# Tracker_V3.net
KiCad netlist of a schematic drawn in EAGLE
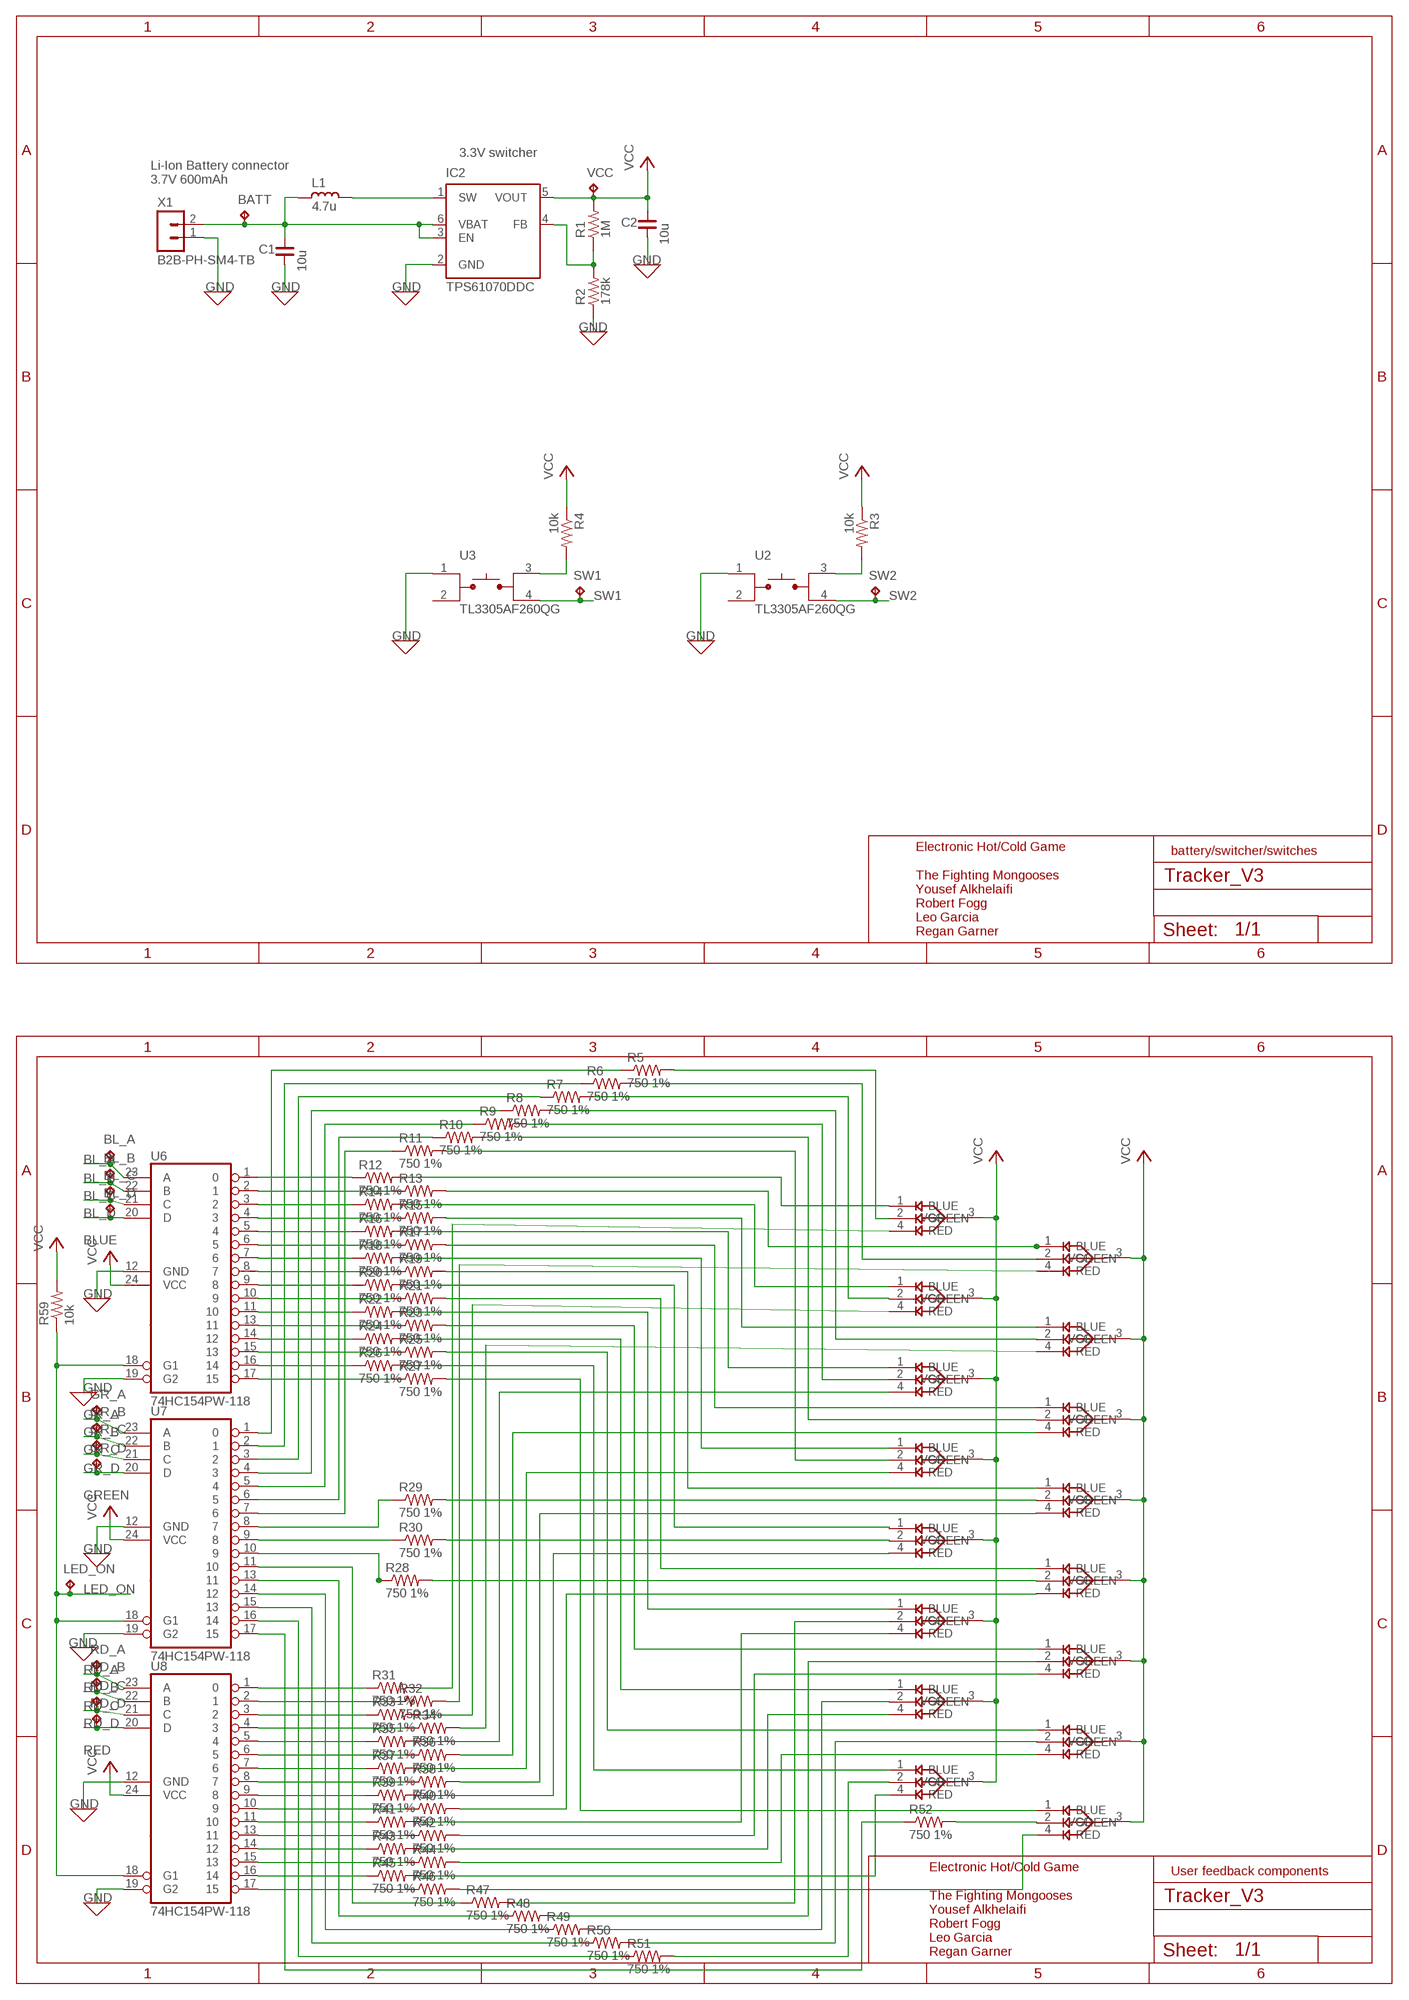
[diagram p0: schematic, sheet 1, part 1 of 2]
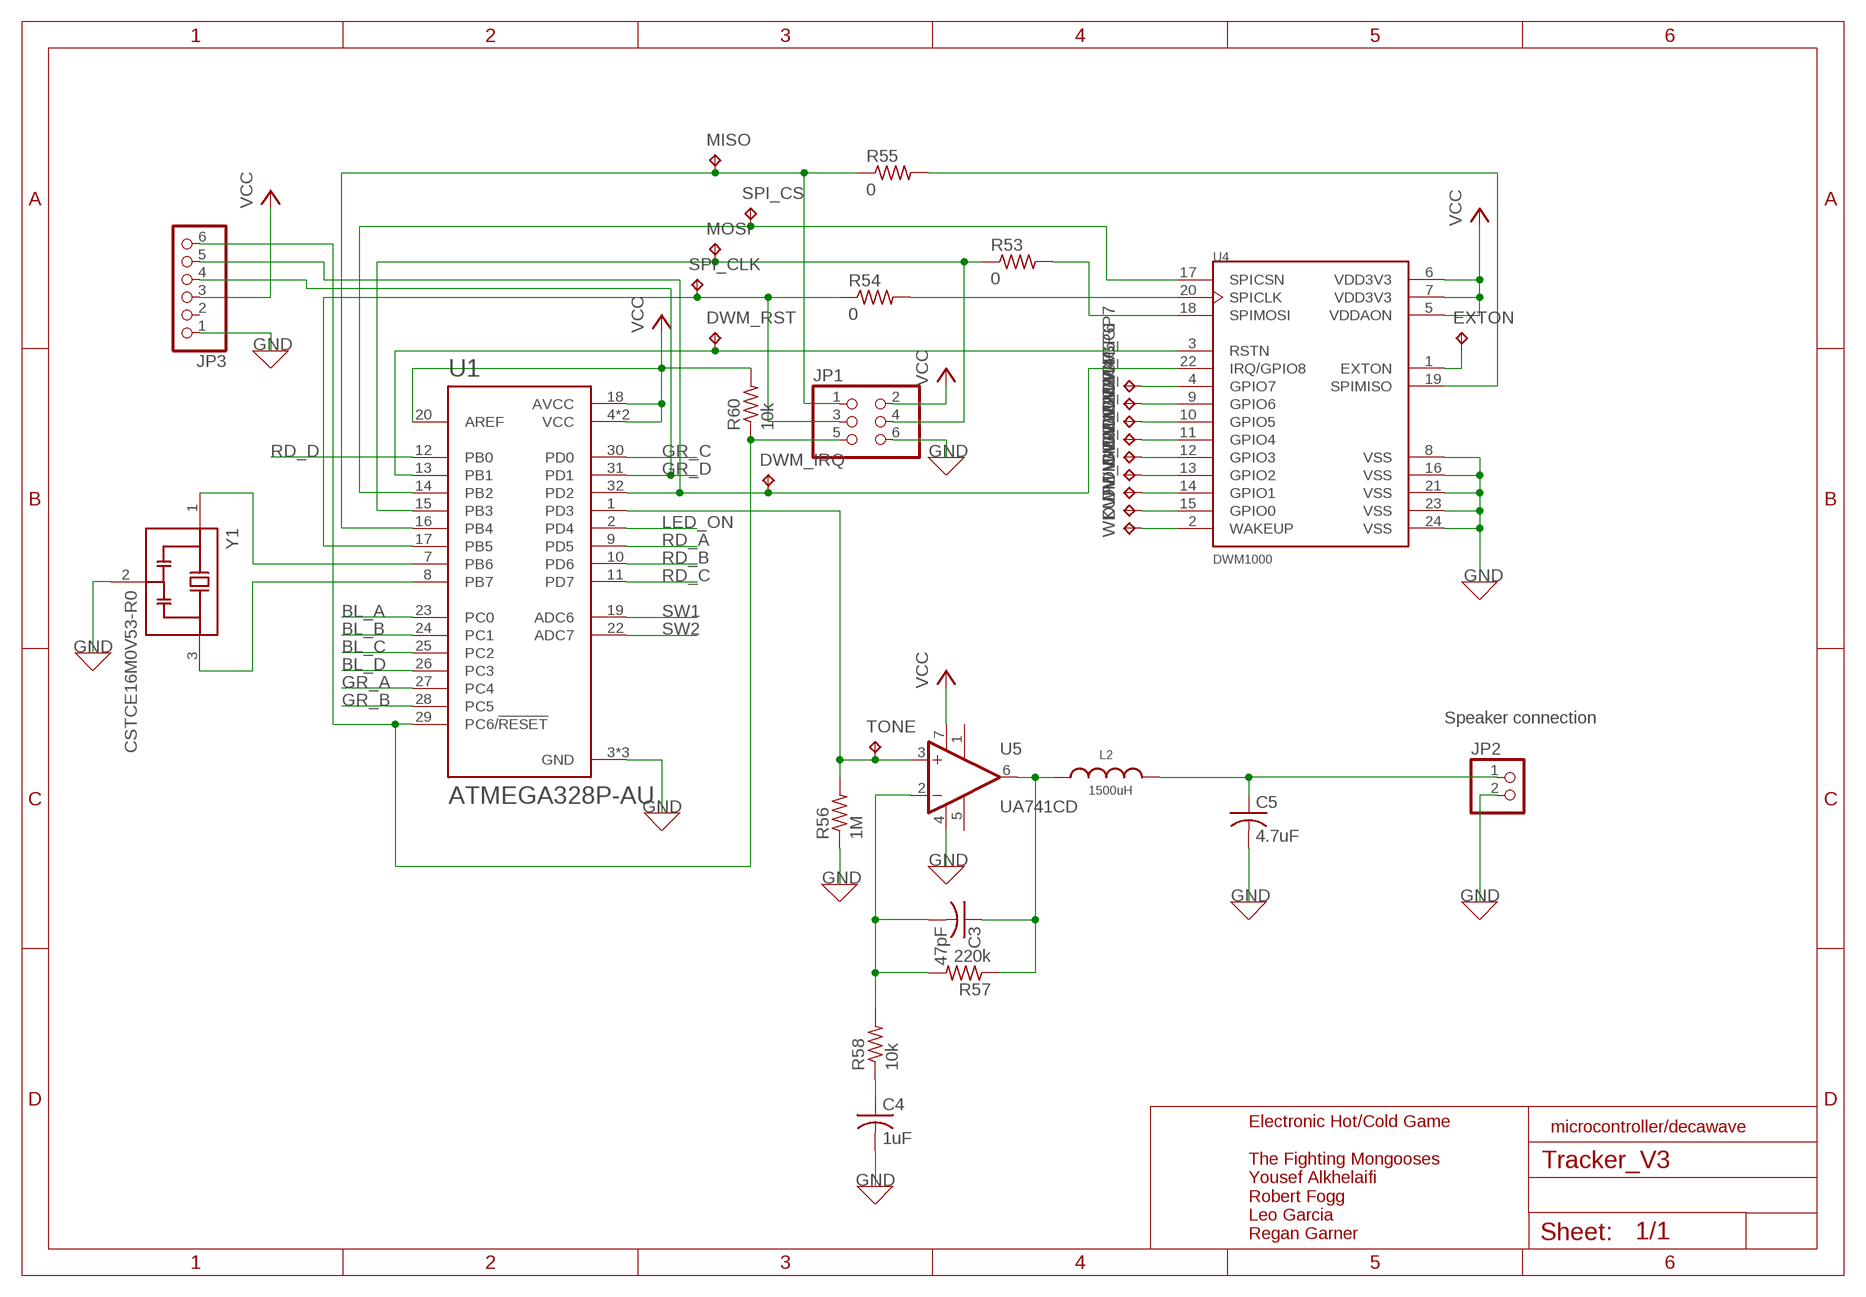
[diagram p1: schematic, sheet 1, part 2 of 2]

(export (version "E")
  (design (tool "Eeschema 10.0.6"))
  (components
    (comp (ref "BATT")
      (value "TPB2,54")
      (footprint "eagle-import:B2,54")
      (libsource (lib "eagle-import") (part "TPB2,54"))
    )
    (comp (ref "BL_A")
      (value "TPB2,54")
      (footprint "eagle-import:B2,54")
      (libsource (lib "eagle-import") (part "TPB2,54"))
    )
    (comp (ref "BL_B")
      (value "TPB2,54")
      (footprint "eagle-import:B2,54")
      (libsource (lib "eagle-import") (part "TPB2,54"))
    )
    (comp (ref "BL_C")
      (value "TPB2,54")
      (footprint "eagle-import:B2,54")
      (libsource (lib "eagle-import") (part "TPB2,54"))
    )
    (comp (ref "BL_D")
      (value "TPB2,54")
      (footprint "eagle-import:B2,54")
      (libsource (lib "eagle-import") (part "TPB2,54"))
    )
    (comp (ref "C1")
      (value "10u")
      (footprint "eagle-import:C0603")
      (fields (field (name "C1") "10uF"))
      (libsource (lib "eagle-import") (part "C_0603"))
    )
    (comp (ref "C2")
      (value "10u")
      (footprint "eagle-import:C0603")
      (fields (field (name "C1") "10uF"))
      (libsource (lib "eagle-import") (part "C_0603"))
    )
    (comp (ref "C3")
      (value "47pF")
      (footprint "eagle-import:C0402")
      (libsource (lib "eagle-import") (part "C-USC0402"))
    )
    (comp (ref "C4")
      (value "1uF")
      (footprint "eagle-import:C0402")
      (libsource (lib "eagle-import") (part "C-USC0402"))
    )
    (comp (ref "C5")
      (value "4.7uF")
      (footprint "eagle-import:C0402")
      (libsource (lib "eagle-import") (part "C-USC0402"))
    )
    (comp (ref "D1")
      (value "LED_EAST1616RGBA3")
      (footprint "eagle-import:LED_EAST1616RGBA3")
      (libsource (lib "eagle-import") (part "LED_EAST1616RGBA3"))
    )
    (comp (ref "D2")
      (value "LED_EAST1616RGBA3")
      (footprint "eagle-import:LED_EAST1616RGBA3")
      (libsource (lib "eagle-import") (part "LED_EAST1616RGBA3"))
    )
    (comp (ref "D3")
      (value "LED_EAST1616RGBA3")
      (footprint "eagle-import:LED_EAST1616RGBA3")
      (libsource (lib "eagle-import") (part "LED_EAST1616RGBA3"))
    )
    (comp (ref "D4")
      (value "LED_EAST1616RGBA3")
      (footprint "eagle-import:LED_EAST1616RGBA3")
      (libsource (lib "eagle-import") (part "LED_EAST1616RGBA3"))
    )
    (comp (ref "D5")
      (value "LED_EAST1616RGBA3")
      (footprint "eagle-import:LED_EAST1616RGBA3")
      (libsource (lib "eagle-import") (part "LED_EAST1616RGBA3"))
    )
    (comp (ref "D6")
      (value "LED_EAST1616RGBA3")
      (footprint "eagle-import:LED_EAST1616RGBA3")
      (libsource (lib "eagle-import") (part "LED_EAST1616RGBA3"))
    )
    (comp (ref "D7")
      (value "LED_EAST1616RGBA3")
      (footprint "eagle-import:LED_EAST1616RGBA3")
      (libsource (lib "eagle-import") (part "LED_EAST1616RGBA3"))
    )
    (comp (ref "D8")
      (value "LED_EAST1616RGBA3")
      (footprint "eagle-import:LED_EAST1616RGBA3")
      (libsource (lib "eagle-import") (part "LED_EAST1616RGBA3"))
    )
    (comp (ref "D9")
      (value "LED_EAST1616RGBA3")
      (footprint "eagle-import:LED_EAST1616RGBA3")
      (libsource (lib "eagle-import") (part "LED_EAST1616RGBA3"))
    )
    (comp (ref "D10")
      (value "LED_EAST1616RGBA3")
      (footprint "eagle-import:LED_EAST1616RGBA3")
      (libsource (lib "eagle-import") (part "LED_EAST1616RGBA3"))
    )
    (comp (ref "D11")
      (value "LED_EAST1616RGBA3")
      (footprint "eagle-import:LED_EAST1616RGBA3")
      (libsource (lib "eagle-import") (part "LED_EAST1616RGBA3"))
    )
    (comp (ref "D12")
      (value "LED_EAST1616RGBA3")
      (footprint "eagle-import:LED_EAST1616RGBA3")
      (libsource (lib "eagle-import") (part "LED_EAST1616RGBA3"))
    )
    (comp (ref "D13")
      (value "LED_EAST1616RGBA3")
      (footprint "eagle-import:LED_EAST1616RGBA3")
      (libsource (lib "eagle-import") (part "LED_EAST1616RGBA3"))
    )
    (comp (ref "D14")
      (value "LED_EAST1616RGBA3")
      (footprint "eagle-import:LED_EAST1616RGBA3")
      (libsource (lib "eagle-import") (part "LED_EAST1616RGBA3"))
    )
    (comp (ref "D15")
      (value "LED_EAST1616RGBA3")
      (footprint "eagle-import:LED_EAST1616RGBA3")
      (libsource (lib "eagle-import") (part "LED_EAST1616RGBA3"))
    )
    (comp (ref "D16")
      (value "LED_EAST1616RGBA3")
      (footprint "eagle-import:LED_EAST1616RGBA3")
      (libsource (lib "eagle-import") (part "LED_EAST1616RGBA3"))
    )
    (comp (ref "DWM_GP0")
      (value "TPB2,54")
      (footprint "eagle-import:B2,54")
      (libsource (lib "eagle-import") (part "TPB2,54"))
    )
    (comp (ref "DWM_GP1")
      (value "TPB2,54")
      (footprint "eagle-import:B2,54")
      (libsource (lib "eagle-import") (part "TPB2,54"))
    )
    (comp (ref "DWM_GP2")
      (value "TPB2,54")
      (footprint "eagle-import:B2,54")
      (libsource (lib "eagle-import") (part "TPB2,54"))
    )
    (comp (ref "DWM_GP3")
      (value "TPB2,54")
      (footprint "eagle-import:B2,54")
      (libsource (lib "eagle-import") (part "TPB2,54"))
    )
    (comp (ref "DWM_GP4")
      (value "TPB2,54")
      (footprint "eagle-import:B2,54")
      (libsource (lib "eagle-import") (part "TPB2,54"))
    )
    (comp (ref "DWM_GP5")
      (value "TPB2,54")
      (footprint "eagle-import:B2,54")
      (libsource (lib "eagle-import") (part "TPB2,54"))
    )
    (comp (ref "DWM_GP6")
      (value "TPB2,54")
      (footprint "eagle-import:B2,54")
      (libsource (lib "eagle-import") (part "TPB2,54"))
    )
    (comp (ref "DWM_GP7")
      (value "TPB2,54")
      (footprint "eagle-import:B2,54")
      (libsource (lib "eagle-import") (part "TPB2,54"))
    )
    (comp (ref "DWM_IRQ")
      (value "TPB2,54")
      (footprint "eagle-import:B2,54")
      (libsource (lib "eagle-import") (part "TPB2,54"))
    )
    (comp (ref "DWM_RST")
      (value "TPB2,54")
      (footprint "eagle-import:B2,54")
      (libsource (lib "eagle-import") (part "TPB2,54"))
    )
    (comp (ref "EXTON")
      (value "TPB2,54")
      (footprint "eagle-import:B2,54")
      (libsource (lib "eagle-import") (part "TPB2,54"))
    )
    (comp (ref "GR_A")
      (value "TPB2,54")
      (footprint "eagle-import:B2,54")
      (libsource (lib "eagle-import") (part "TPB2,54"))
    )
    (comp (ref "GR_B")
      (value "TPB2,54")
      (footprint "eagle-import:B2,54")
      (libsource (lib "eagle-import") (part "TPB2,54"))
    )
    (comp (ref "GR_C")
      (value "TPB2,54")
      (footprint "eagle-import:B2,54")
      (libsource (lib "eagle-import") (part "TPB2,54"))
    )
    (comp (ref "GR_D")
      (value "TPB2,54")
      (footprint "eagle-import:B2,54")
      (libsource (lib "eagle-import") (part "TPB2,54"))
    )
    (comp (ref "IC2")
      (value "TPS61070DDC")
      (footprint "eagle-import:TSOT23-6_DDC")
      (fields (field (name "MPN") "TPS61070DDCR"))
      (libsource (lib "eagle-import") (part "TPS6107DDC0"))
    )
    (comp (ref "JP1")
      (value "PINHD-2X3")
      (footprint "eagle-import:2X03")
      (libsource (lib "eagle-import") (part "PINHD-2X3"))
    )
    (comp (ref "JP2")
      (value "PINHD-1X2")
      (footprint "eagle-import:1X02")
      (libsource (lib "eagle-import") (part "PINHD-1X2"))
    )
    (comp (ref "JP3")
      (value "PINHD-1X6")
      (footprint "eagle-import:1X06")
      (libsource (lib "eagle-import") (part "PINHD-1X6"))
    )
    (comp (ref "L1")
      (value "4.7u")
      (footprint "eagle-import:L0603")
      (fields (field (name "L1") "4.7uH"))
      (libsource (lib "eagle-import") (part "L_0603"))
    )
    (comp (ref "L2")
      (value "1500uH")
      (footprint "eagle-import:WE-TPC_4828")
      (libsource (lib "eagle-import") (part "WE-TPC_4828_744043152"))
    )
    (comp (ref "LED_ON")
      (value "TPB2,54")
      (footprint "eagle-import:B2,54")
      (libsource (lib "eagle-import") (part "TPB2,54"))
    )
    (comp (ref "MISO")
      (value "TPB2,54")
      (footprint "eagle-import:B2,54")
      (libsource (lib "eagle-import") (part "TPB2,54"))
    )
    (comp (ref "MOSI")
      (value "TPB2,54")
      (footprint "eagle-import:B2,54")
      (libsource (lib "eagle-import") (part "TPB2,54"))
    )
    (comp (ref "R1")
      (value "1M")
      (footprint "eagle-import:R0603")
      (libsource (lib "eagle-import") (part "R_0603"))
    )
    (comp (ref "R2")
      (value "178k")
      (footprint "eagle-import:R0603")
      (libsource (lib "eagle-import") (part "R_0603"))
    )
    (comp (ref "R3")
      (value "10k")
      (footprint "eagle-import:R0603")
      (libsource (lib "eagle-import") (part "resistor_348_R-US_R0603"))
    )
    (comp (ref "R4")
      (value "10k")
      (footprint "eagle-import:R0603")
      (libsource (lib "eagle-import") (part "resistor_348_R-US_R0603"))
    )
    (comp (ref "R5")
      (value "750 1%")
      (footprint "eagle-import:R0402")
      (libsource (lib "eagle-import") (part "resistor_348_R-US_R0402"))
    )
    (comp (ref "R6")
      (value "750 1%")
      (footprint "eagle-import:R0402")
      (libsource (lib "eagle-import") (part "resistor_348_R-US_R0402"))
    )
    (comp (ref "R7")
      (value "750 1%")
      (footprint "eagle-import:R0402")
      (libsource (lib "eagle-import") (part "resistor_348_R-US_R0402"))
    )
    (comp (ref "R8")
      (value "750 1%")
      (footprint "eagle-import:R0402")
      (libsource (lib "eagle-import") (part "resistor_348_R-US_R0402"))
    )
    (comp (ref "R9")
      (value "750 1%")
      (footprint "eagle-import:R0402")
      (libsource (lib "eagle-import") (part "resistor_348_R-US_R0402"))
    )
    (comp (ref "R10")
      (value "750 1%")
      (footprint "eagle-import:R0402")
      (libsource (lib "eagle-import") (part "resistor_348_R-US_R0402"))
    )
    (comp (ref "R11")
      (value "750 1%")
      (footprint "eagle-import:R0402")
      (libsource (lib "eagle-import") (part "resistor_348_R-US_R0402"))
    )
    (comp (ref "R12")
      (value "750 1%")
      (footprint "eagle-import:R0402")
      (libsource (lib "eagle-import") (part "resistor_348_R-US_R0402"))
    )
    (comp (ref "R13")
      (value "750 1%")
      (footprint "eagle-import:R0402")
      (libsource (lib "eagle-import") (part "resistor_348_R-US_R0402"))
    )
    (comp (ref "R14")
      (value "750 1%")
      (footprint "eagle-import:R0402")
      (libsource (lib "eagle-import") (part "resistor_348_R-US_R0402"))
    )
    (comp (ref "R15")
      (value "750 1%")
      (footprint "eagle-import:R0402")
      (libsource (lib "eagle-import") (part "resistor_348_R-US_R0402"))
    )
    (comp (ref "R16")
      (value "750 1%")
      (footprint "eagle-import:R0402")
      (libsource (lib "eagle-import") (part "resistor_348_R-US_R0402"))
    )
    (comp (ref "R17")
      (value "750 1%")
      (footprint "eagle-import:R0402")
      (libsource (lib "eagle-import") (part "resistor_348_R-US_R0402"))
    )
    (comp (ref "R18")
      (value "750 1%")
      (footprint "eagle-import:R0402")
      (libsource (lib "eagle-import") (part "resistor_348_R-US_R0402"))
    )
    (comp (ref "R19")
      (value "750 1%")
      (footprint "eagle-import:R0402")
      (libsource (lib "eagle-import") (part "resistor_348_R-US_R0402"))
    )
    (comp (ref "R20")
      (value "750 1%")
      (footprint "eagle-import:R0402")
      (libsource (lib "eagle-import") (part "resistor_348_R-US_R0402"))
    )
    (comp (ref "R21")
      (value "750 1%")
      (footprint "eagle-import:R0402")
      (libsource (lib "eagle-import") (part "resistor_348_R-US_R0402"))
    )
    (comp (ref "R22")
      (value "750 1%")
      (footprint "eagle-import:R0402")
      (libsource (lib "eagle-import") (part "resistor_348_R-US_R0402"))
    )
    (comp (ref "R23")
      (value "750 1%")
      (footprint "eagle-import:R0402")
      (libsource (lib "eagle-import") (part "resistor_348_R-US_R0402"))
    )
    (comp (ref "R24")
      (value "750 1%")
      (footprint "eagle-import:R0402")
      (libsource (lib "eagle-import") (part "resistor_348_R-US_R0402"))
    )
    (comp (ref "R25")
      (value "750 1%")
      (footprint "eagle-import:R0402")
      (libsource (lib "eagle-import") (part "resistor_348_R-US_R0402"))
    )
    (comp (ref "R26")
      (value "750 1%")
      (footprint "eagle-import:R0402")
      (libsource (lib "eagle-import") (part "resistor_348_R-US_R0402"))
    )
    (comp (ref "R27")
      (value "750 1%")
      (footprint "eagle-import:R0402")
      (libsource (lib "eagle-import") (part "resistor_348_R-US_R0402"))
    )
    (comp (ref "R28")
      (value "750 1%")
      (footprint "eagle-import:R0402")
      (libsource (lib "eagle-import") (part "resistor_348_R-US_R0402"))
    )
    (comp (ref "R29")
      (value "750 1%")
      (footprint "eagle-import:R0402")
      (libsource (lib "eagle-import") (part "resistor_348_R-US_R0402"))
    )
    (comp (ref "R30")
      (value "750 1%")
      (footprint "eagle-import:R0402")
      (libsource (lib "eagle-import") (part "resistor_348_R-US_R0402"))
    )
    (comp (ref "R31")
      (value "750 1%")
      (footprint "eagle-import:R0402")
      (libsource (lib "eagle-import") (part "resistor_348_R-US_R0402"))
    )
    (comp (ref "R32")
      (value "750 1%")
      (footprint "eagle-import:R0402")
      (libsource (lib "eagle-import") (part "resistor_348_R-US_R0402"))
    )
    (comp (ref "R33")
      (value "750 1%")
      (footprint "eagle-import:R0402")
      (libsource (lib "eagle-import") (part "resistor_348_R-US_R0402"))
    )
    (comp (ref "R34")
      (value "750 1%")
      (footprint "eagle-import:R0402")
      (libsource (lib "eagle-import") (part "resistor_348_R-US_R0402"))
    )
    (comp (ref "R35")
      (value "750 1%")
      (footprint "eagle-import:R0402")
      (libsource (lib "eagle-import") (part "resistor_348_R-US_R0402"))
    )
    (comp (ref "R36")
      (value "750 1%")
      (footprint "eagle-import:R0402")
      (libsource (lib "eagle-import") (part "resistor_348_R-US_R0402"))
    )
    (comp (ref "R37")
      (value "750 1%")
      (footprint "eagle-import:R0402")
      (libsource (lib "eagle-import") (part "resistor_348_R-US_R0402"))
    )
    (comp (ref "R38")
      (value "750 1%")
      (footprint "eagle-import:R0402")
      (libsource (lib "eagle-import") (part "resistor_348_R-US_R0402"))
    )
    (comp (ref "R39")
      (value "750 1%")
      (footprint "eagle-import:R0402")
      (libsource (lib "eagle-import") (part "resistor_348_R-US_R0402"))
    )
    (comp (ref "R40")
      (value "750 1%")
      (footprint "eagle-import:R0402")
      (libsource (lib "eagle-import") (part "resistor_348_R-US_R0402"))
    )
    (comp (ref "R41")
      (value "750 1%")
      (footprint "eagle-import:R0402")
      (libsource (lib "eagle-import") (part "resistor_348_R-US_R0402"))
    )
    (comp (ref "R42")
      (value "750 1%")
      (footprint "eagle-import:R0402")
      (libsource (lib "eagle-import") (part "resistor_348_R-US_R0402"))
    )
    (comp (ref "R43")
      (value "750 1%")
      (footprint "eagle-import:R0402")
      (libsource (lib "eagle-import") (part "resistor_348_R-US_R0402"))
    )
    (comp (ref "R44")
      (value "750 1%")
      (footprint "eagle-import:R0402")
      (libsource (lib "eagle-import") (part "resistor_348_R-US_R0402"))
    )
    (comp (ref "R45")
      (value "750 1%")
      (footprint "eagle-import:R0402")
      (libsource (lib "eagle-import") (part "resistor_348_R-US_R0402"))
    )
    (comp (ref "R46")
      (value "750 1%")
      (footprint "eagle-import:R0402")
      (libsource (lib "eagle-import") (part "resistor_348_R-US_R0402"))
    )
    (comp (ref "R47")
      (value "750 1%")
      (footprint "eagle-import:R0402")
      (libsource (lib "eagle-import") (part "resistor_348_R-US_R0402"))
    )
    (comp (ref "R48")
      (value "750 1%")
      (footprint "eagle-import:R0402")
      (libsource (lib "eagle-import") (part "resistor_348_R-US_R0402"))
    )
    (comp (ref "R49")
      (value "750 1%")
      (footprint "eagle-import:R0402")
      (libsource (lib "eagle-import") (part "resistor_348_R-US_R0402"))
    )
    (comp (ref "R50")
      (value "750 1%")
      (footprint "eagle-import:R0402")
      (libsource (lib "eagle-import") (part "resistor_348_R-US_R0402"))
    )
    (comp (ref "R51")
      (value "750 1%")
      (footprint "eagle-import:R0402")
      (libsource (lib "eagle-import") (part "resistor_348_R-US_R0402"))
    )
    (comp (ref "R52")
      (value "750 1%")
      (footprint "eagle-import:R0402")
      (libsource (lib "eagle-import") (part "resistor_348_R-US_R0402"))
    )
    (comp (ref "R53")
      (value "0")
      (footprint "eagle-import:R0402")
      (libsource (lib "eagle-import") (part "resistor_348_R-US_R0402"))
    )
    (comp (ref "R54")
      (value "0")
      (footprint "eagle-import:R0402")
      (libsource (lib "eagle-import") (part "resistor_348_R-US_R0402"))
    )
    (comp (ref "R55")
      (value "0")
      (footprint "eagle-import:R0402")
      (libsource (lib "eagle-import") (part "resistor_348_R-US_R0402"))
    )
    (comp (ref "R56")
      (value "1M")
      (footprint "eagle-import:R0603")
      (libsource (lib "eagle-import") (part "R-US_R0603"))
    )
    (comp (ref "R57")
      (value "220k")
      (footprint "eagle-import:R0603")
      (libsource (lib "eagle-import") (part "R-US_R0603"))
    )
    (comp (ref "R58")
      (value "10k")
      (footprint "eagle-import:R0603")
      (libsource (lib "eagle-import") (part "R-US_R0603"))
    )
    (comp (ref "R59")
      (value "10k")
      (footprint "eagle-import:R0603")
      (libsource (lib "eagle-import") (part "R-US_R0603"))
    )
    (comp (ref "R60")
      (value "10k")
      (footprint "eagle-import:R0603")
      (libsource (lib "eagle-import") (part "R-US_R0603"))
    )
    (comp (ref "RD_A")
      (value "TPB2,54")
      (footprint "eagle-import:B2,54")
      (libsource (lib "eagle-import") (part "TPB2,54"))
    )
    (comp (ref "RD_B")
      (value "TPB2,54")
      (footprint "eagle-import:B2,54")
      (libsource (lib "eagle-import") (part "TPB2,54"))
    )
    (comp (ref "RD_C")
      (value "TPB2,54")
      (footprint "eagle-import:B2,54")
      (libsource (lib "eagle-import") (part "TPB2,54"))
    )
    (comp (ref "RD_D")
      (value "TPB2,54")
      (footprint "eagle-import:B2,54")
      (libsource (lib "eagle-import") (part "TPB2,54"))
    )
    (comp (ref "SPI_CLK")
      (value "TPB2,54")
      (footprint "eagle-import:B2,54")
      (libsource (lib "eagle-import") (part "TPB2,54"))
    )
    (comp (ref "SPI_CS")
      (value "TPB2,54")
      (footprint "eagle-import:B2,54")
      (libsource (lib "eagle-import") (part "TPB2,54"))
    )
    (comp (ref "SW1")
      (value "TPB2,54")
      (footprint "eagle-import:B2,54")
      (libsource (lib "eagle-import") (part "TPB2,54"))
    )
    (comp (ref "SW2")
      (value "TPB2,54")
      (footprint "eagle-import:B2,54")
      (libsource (lib "eagle-import") (part "TPB2,54"))
    )
    (comp (ref "TONE")
      (value "TPB2,54")
      (footprint "eagle-import:B2,54")
      (libsource (lib "eagle-import") (part "TPB2,54"))
    )
    (comp (ref "U1")
      (value "ATMEGA328P-AU")
      (footprint "eagle-import:QFP80P900X900X120-32N")
      (fields (field (name "MF") "Microchip Technology"))
      (libsource (lib "eagle-import") (part "ATMEGA328P-AU"))
    )
    (comp (ref "U2")
      (value "TL3305AF260QG")
      (footprint "eagle-import:SW_TL3305AF260QG")
      (fields (field (name "MF") "E-Switch"))
      (libsource (lib "eagle-import") (part "TL3305AF260QG"))
    )
    (comp (ref "U3")
      (value "TL3305AF260QG")
      (footprint "eagle-import:SW_TL3305AF260QG")
      (fields (field (name "MF") "E-Switch"))
      (libsource (lib "eagle-import") (part "TL3305AF260QG"))
    )
    (comp (ref "U4")
      (value "DWM1000")
      (footprint "eagle-import:XCVR_DWM1000")
      (fields (field (name "MF") "Decawave Limited"))
      (libsource (lib "eagle-import") (part "DWM1000"))
    )
    (comp (ref "U5")
      (value "UA741CD")
      (footprint "eagle-import:SOIC127P600X175-8N")
      (fields (field (name "MF") "STMicroelectronics"))
      (libsource (lib "eagle-import") (part "UA741CD"))
    )
    (comp (ref "U6")
      (value "74HC154PW-118")
      (footprint "eagle-import:SOP65P640X110-24N")
      (libsource (lib "eagle-import") (part "74HC154PW-118"))
    )
    (comp (ref "U7")
      (value "74HC154PW-118")
      (footprint "eagle-import:SOP65P640X110-24N")
      (libsource (lib "eagle-import") (part "74HC154PW-118"))
    )
    (comp (ref "U8")
      (value "74HC154PW-118")
      (footprint "eagle-import:SOP65P640X110-24N")
      (libsource (lib "eagle-import") (part "74HC154PW-118"))
    )
    (comp (ref "VCC")
      (value "TPB2,54")
      (footprint "eagle-import:B2,54")
      (libsource (lib "eagle-import") (part "TPB2,54"))
    )
    (comp (ref "WKUP")
      (value "TPB2,54")
      (footprint "eagle-import:B2,54")
      (libsource (lib "eagle-import") (part "TPB2,54"))
    )
    (comp (ref "X1")
      (value "B2B-PH-SM4-TB")
      (footprint "eagle-import:B2B-PH-SM4-TB")
      (libsource (lib "eagle-import") (part "B2B-PH-SM4-TB"))
    )
    (comp (ref "Y1")
      (value "CSTCE16M0V53-R0")
      (footprint "eagle-import:OSC_CSTCE16M0V53-R0")
      (fields (field (name "MF") "Murata"))
      (libsource (lib "eagle-import") (part "CSTCE16M0V53-R0"))
    )
  )
  (nets
    (net (code "1") (name "/BL_A") (class "Default")
      (node (ref "BL_A") (pin "TP") (pinfunction "TP_TP") (pintype "input"))
      (node (ref "U1") (pin "23") (pinfunction "PC0_23") (pintype "bidirectional"))
      (node (ref "U6") (pin "23") (pinfunction "A_23") (pintype "input"))
    )
    (net (code "2") (name "/BL_B") (class "Default")
      (node (ref "BL_B") (pin "TP") (pinfunction "TP_TP") (pintype "input"))
      (node (ref "U1") (pin "24") (pinfunction "PC1_24") (pintype "bidirectional"))
      (node (ref "U6") (pin "22") (pinfunction "B_22") (pintype "input"))
    )
    (net (code "3") (name "/BL_C") (class "Default")
      (node (ref "BL_C") (pin "TP") (pinfunction "TP_TP") (pintype "input"))
      (node (ref "U1") (pin "25") (pinfunction "PC2_25") (pintype "bidirectional"))
      (node (ref "U6") (pin "21") (pinfunction "C_21") (pintype "input"))
    )
    (net (code "4") (name "/BL_D") (class "Default")
      (node (ref "BL_D") (pin "TP") (pinfunction "TP_TP") (pintype "input"))
      (node (ref "U1") (pin "26") (pinfunction "PC3_26") (pintype "bidirectional"))
      (node (ref "U6") (pin "20") (pinfunction "D_20") (pintype "input"))
    )
    (net (code "5") (name "/GR_A") (class "Default")
      (node (ref "GR_A") (pin "TP") (pinfunction "TP_TP") (pintype "input"))
      (node (ref "U1") (pin "27") (pinfunction "PC4_27") (pintype "bidirectional"))
      (node (ref "U7") (pin "23") (pinfunction "A_23") (pintype "input"))
    )
    (net (code "6") (name "/GR_B") (class "Default")
      (node (ref "GR_B") (pin "TP") (pinfunction "TP_TP") (pintype "input"))
      (node (ref "U1") (pin "28") (pinfunction "PC5_28") (pintype "bidirectional"))
      (node (ref "U7") (pin "22") (pinfunction "B_22") (pintype "input"))
    )
    (net (code "7") (name "/GR_C") (class "Default")
      (node (ref "GR_C") (pin "TP") (pinfunction "TP_TP") (pintype "input"))
      (node (ref "U1") (pin "30") (pinfunction "PD0_30") (pintype "bidirectional"))
      (node (ref "U7") (pin "21") (pinfunction "C_21") (pintype "input"))
    )
    (net (code "8") (name "/GR_D") (class "Default")
      (node (ref "GR_D") (pin "TP") (pinfunction "TP_TP") (pintype "input"))
      (node (ref "JP3") (pin "4") (pinfunction "4_4") (pintype "passive"))
      (node (ref "U1") (pin "31") (pinfunction "PD1_31") (pintype "bidirectional"))
      (node (ref "U7") (pin "20") (pinfunction "D_20") (pintype "input"))
    )
    (net (code "9") (name "/LED_ON") (class "Default")
      (node (ref "LED_ON") (pin "TP") (pinfunction "TP_TP") (pintype "input"))
      (node (ref "R59") (pin "1") (pinfunction "1_1") (pintype "passive"))
      (node (ref "U1") (pin "2") (pinfunction "PD4_2") (pintype "bidirectional"))
      (node (ref "U6") (pin "18") (pinfunction "G1_18") (pintype "input"))
      (node (ref "U7") (pin "18") (pinfunction "G1_18") (pintype "input"))
      (node (ref "U8") (pin "18") (pinfunction "G1_18") (pintype "input"))
    )
    (net (code "10") (name "/RD_A") (class "Default")
      (node (ref "RD_A") (pin "TP") (pinfunction "TP_TP") (pintype "input"))
      (node (ref "U1") (pin "9") (pinfunction "PD5_9") (pintype "bidirectional"))
      (node (ref "U8") (pin "23") (pinfunction "A_23") (pintype "input"))
    )
    (net (code "11") (name "/RD_B") (class "Default")
      (node (ref "RD_B") (pin "TP") (pinfunction "TP_TP") (pintype "input"))
      (node (ref "U1") (pin "10") (pinfunction "PD6_10") (pintype "bidirectional"))
      (node (ref "U8") (pin "22") (pinfunction "B_22") (pintype "input"))
    )
    (net (code "12") (name "/RD_C") (class "Default")
      (node (ref "RD_C") (pin "TP") (pinfunction "TP_TP") (pintype "input"))
      (node (ref "U1") (pin "11") (pinfunction "PD7_11") (pintype "bidirectional"))
      (node (ref "U8") (pin "21") (pinfunction "C_21") (pintype "input"))
    )
    (net (code "13") (name "/RD_D") (class "Default")
      (node (ref "RD_D") (pin "TP") (pinfunction "TP_TP") (pintype "input"))
      (node (ref "U1") (pin "12") (pinfunction "PB0_12") (pintype "bidirectional"))
      (node (ref "U8") (pin "20") (pinfunction "D_20") (pintype "input"))
    )
    (net (code "14") (name "/SW1") (class "Default")
      (node (ref "SW1") (pin "TP") (pinfunction "TP_TP") (pintype "input"))
      (node (ref "U1") (pin "19") (pinfunction "ADC6_19") (pintype "bidirectional"))
      (node (ref "U3") (pin "4") (pinfunction "4_4") (pintype "passive"))
    )
    (net (code "15") (name "/SW2") (class "Default")
      (node (ref "SW2") (pin "TP") (pinfunction "TP_TP") (pintype "input"))
      (node (ref "U1") (pin "22") (pinfunction "ADC7_22") (pintype "bidirectional"))
      (node (ref "U2") (pin "4") (pinfunction "4_4") (pintype "passive"))
    )
    (net (code "16") (name "GND") (class "Default")
      (node (ref "C1") (pin "1") (pinfunction "1_1") (pintype "passive"))
      (node (ref "C2") (pin "1") (pinfunction "1_1") (pintype "passive"))
      (node (ref "C4") (pin "2") (pinfunction "2_2") (pintype "passive"))
      (node (ref "C5") (pin "2") (pinfunction "2_2") (pintype "passive"))
      (node (ref "IC2") (pin "2") (pinfunction "GND_2") (pintype "power_in"))
      (node (ref "JP1") (pin "6") (pinfunction "6_6") (pintype "passive"))
      (node (ref "JP2") (pin "2") (pinfunction "2_2") (pintype "passive"))
      (node (ref "JP3") (pin "1") (pinfunction "1_1") (pintype "passive"))
      (node (ref "R2") (pin "1") (pinfunction "1_1") (pintype "passive"))
      (node (ref "R56") (pin "1") (pinfunction "1_1") (pintype "passive"))
      (node (ref "U1") (pin "21") (pinfunction "GND_21") (pintype "power_in"))
      (node (ref "U1") (pin "3") (pinfunction "GND_3") (pintype "power_in"))
      (node (ref "U1") (pin "5") (pinfunction "GND_5") (pintype "power_in"))
      (node (ref "U2") (pin "1") (pinfunction "1_1") (pintype "passive"))
      (node (ref "U3") (pin "1") (pinfunction "1_1") (pintype "passive"))
      (node (ref "U4") (pin "16") (pinfunction "VSS_16") (pintype "power_in"))
      (node (ref "U4") (pin "21") (pinfunction "VSS_21") (pintype "power_in"))
      (node (ref "U4") (pin "23") (pinfunction "VSS_23") (pintype "power_in"))
      (node (ref "U4") (pin "24") (pinfunction "VSS_24") (pintype "power_in"))
      (node (ref "U4") (pin "8") (pinfunction "VSS_8") (pintype "power_in"))
      (node (ref "U5") (pin "4") (pinfunction "VCC-_4") (pintype "power_in"))
      (node (ref "U6") (pin "12") (pinfunction "GND_12") (pintype "power_in"))
      (node (ref "U6") (pin "19") (pinfunction "G2_19") (pintype "input"))
      (node (ref "U7") (pin "12") (pinfunction "GND_12") (pintype "power_in"))
      (node (ref "U7") (pin "19") (pinfunction "G2_19") (pintype "input"))
      (node (ref "U8") (pin "12") (pinfunction "GND_12") (pintype "power_in"))
      (node (ref "U8") (pin "19") (pinfunction "G2_19") (pintype "input"))
      (node (ref "X1") (pin "1") (pinfunction "1_1") (pintype "passive"))
      (node (ref "Y1") (pin "2") (pinfunction "GND_2") (pintype "power_in"))
    )
    (net (code "17") (name "Net-(C4-Pad1)") (class "Default")
      (node (ref "C4") (pin "1") (pinfunction "1_1") (pintype "passive"))
      (node (ref "R58") (pin "1") (pinfunction "1_1") (pintype "passive"))
    )
    (net (code "18") (name "Net-(C5-Pad1)") (class "Default")
      (node (ref "C5") (pin "1") (pinfunction "1_1") (pintype "passive"))
      (node (ref "JP2") (pin "1") (pinfunction "1_1") (pintype "passive"))
      (node (ref "L2") (pin "2") (pinfunction "2_2") (pintype "passive"))
    )
    (net (code "19") (name "Net-(D1-BLUE)") (class "Default")
      (node (ref "D1") (pin "1") (pinfunction "BLUE_1") (pintype "bidirectional"))
      (node (ref "R12") (pin "2") (pinfunction "2_2") (pintype "passive"))
    )
    (net (code "20") (name "Net-(D1-GREEN)") (class "Default")
      (node (ref "D1") (pin "2") (pinfunction "GREEN_2") (pintype "bidirectional"))
      (node (ref "R5") (pin "2") (pinfunction "2_2") (pintype "passive"))
    )
    (net (code "21") (name "Net-(D1-RED)") (class "Default")
      (node (ref "D1") (pin "4") (pinfunction "RED_4") (pintype "bidirectional"))
      (node (ref "R31") (pin "2") (pinfunction "2_2") (pintype "passive"))
    )
    (net (code "22") (name "Net-(D2-BLUE)") (class "Default")
      (node (ref "D2") (pin "1") (pinfunction "BLUE_1") (pintype "bidirectional"))
      (node (ref "R13") (pin "2") (pinfunction "2_2") (pintype "passive"))
    )
    (net (code "23") (name "Net-(D2-GREEN)") (class "Default")
      (node (ref "D2") (pin "2") (pinfunction "GREEN_2") (pintype "bidirectional"))
      (node (ref "R6") (pin "2") (pinfunction "2_2") (pintype "passive"))
    )
    (net (code "24") (name "Net-(D2-RED)") (class "Default")
      (node (ref "D2") (pin "4") (pinfunction "RED_4") (pintype "bidirectional"))
      (node (ref "R32") (pin "2") (pinfunction "2_2") (pintype "passive"))
    )
    (net (code "25") (name "Net-(D3-BLUE)") (class "Default")
      (node (ref "D3") (pin "1") (pinfunction "BLUE_1") (pintype "bidirectional"))
      (node (ref "R14") (pin "2") (pinfunction "2_2") (pintype "passive"))
    )
    (net (code "26") (name "Net-(D3-GREEN)") (class "Default")
      (node (ref "D3") (pin "2") (pinfunction "GREEN_2") (pintype "bidirectional"))
      (node (ref "R7") (pin "2") (pinfunction "2_2") (pintype "passive"))
    )
    (net (code "27") (name "Net-(D3-RED)") (class "Default")
      (node (ref "D3") (pin "4") (pinfunction "RED_4") (pintype "bidirectional"))
      (node (ref "R33") (pin "2") (pinfunction "2_2") (pintype "passive"))
    )
    (net (code "28") (name "Net-(D4-BLUE)") (class "Default")
      (node (ref "D4") (pin "1") (pinfunction "BLUE_1") (pintype "bidirectional"))
      (node (ref "R15") (pin "2") (pinfunction "2_2") (pintype "passive"))
    )
    (net (code "29") (name "Net-(D4-GREEN)") (class "Default")
      (node (ref "D4") (pin "2") (pinfunction "GREEN_2") (pintype "bidirectional"))
      (node (ref "R8") (pin "2") (pinfunction "2_2") (pintype "passive"))
    )
    (net (code "30") (name "Net-(D4-RED)") (class "Default")
      (node (ref "D4") (pin "4") (pinfunction "RED_4") (pintype "bidirectional"))
      (node (ref "R34") (pin "2") (pinfunction "2_2") (pintype "passive"))
    )
    (net (code "31") (name "Net-(D5-BLUE)") (class "Default")
      (node (ref "D5") (pin "1") (pinfunction "BLUE_1") (pintype "bidirectional"))
      (node (ref "R16") (pin "2") (pinfunction "2_2") (pintype "passive"))
    )
    (net (code "32") (name "Net-(D5-GREEN)") (class "Default")
      (node (ref "D5") (pin "2") (pinfunction "GREEN_2") (pintype "bidirectional"))
      (node (ref "R9") (pin "2") (pinfunction "2_2") (pintype "passive"))
    )
    (net (code "33") (name "Net-(D5-RED)") (class "Default")
      (node (ref "D5") (pin "4") (pinfunction "RED_4") (pintype "bidirectional"))
      (node (ref "R35") (pin "2") (pinfunction "2_2") (pintype "passive"))
    )
    (net (code "34") (name "Net-(D6-BLUE)") (class "Default")
      (node (ref "D6") (pin "1") (pinfunction "BLUE_1") (pintype "bidirectional"))
      (node (ref "R17") (pin "2") (pinfunction "2_2") (pintype "passive"))
    )
    (net (code "35") (name "Net-(D6-GREEN)") (class "Default")
      (node (ref "D6") (pin "2") (pinfunction "GREEN_2") (pintype "bidirectional"))
      (node (ref "R10") (pin "2") (pinfunction "2_2") (pintype "passive"))
    )
    (net (code "36") (name "Net-(D6-RED)") (class "Default")
      (node (ref "D6") (pin "4") (pinfunction "RED_4") (pintype "bidirectional"))
      (node (ref "R36") (pin "2") (pinfunction "2_2") (pintype "passive"))
    )
    (net (code "37") (name "Net-(D7-BLUE)") (class "Default")
      (node (ref "D7") (pin "1") (pinfunction "BLUE_1") (pintype "bidirectional"))
      (node (ref "R18") (pin "2") (pinfunction "2_2") (pintype "passive"))
    )
    (net (code "38") (name "Net-(D7-GREEN)") (class "Default")
      (node (ref "D7") (pin "2") (pinfunction "GREEN_2") (pintype "bidirectional"))
      (node (ref "R11") (pin "2") (pinfunction "2_2") (pintype "passive"))
    )
    (net (code "39") (name "Net-(D7-RED)") (class "Default")
      (node (ref "D7") (pin "4") (pinfunction "RED_4") (pintype "bidirectional"))
      (node (ref "R37") (pin "2") (pinfunction "2_2") (pintype "passive"))
    )
    (net (code "40") (name "Net-(D8-BLUE)") (class "Default")
      (node (ref "D8") (pin "1") (pinfunction "BLUE_1") (pintype "bidirectional"))
      (node (ref "R19") (pin "2") (pinfunction "2_2") (pintype "passive"))
    )
    (net (code "41") (name "Net-(D8-GREEN)") (class "Default")
      (node (ref "D8") (pin "2") (pinfunction "GREEN_2") (pintype "bidirectional"))
      (node (ref "R29") (pin "2") (pinfunction "2_2") (pintype "passive"))
    )
    (net (code "42") (name "Net-(D8-RED)") (class "Default")
      (node (ref "D8") (pin "4") (pinfunction "RED_4") (pintype "bidirectional"))
      (node (ref "R38") (pin "2") (pinfunction "2_2") (pintype "passive"))
    )
    (net (code "43") (name "Net-(D9-BLUE)") (class "Default")
      (node (ref "D9") (pin "1") (pinfunction "BLUE_1") (pintype "bidirectional"))
      (node (ref "R20") (pin "2") (pinfunction "2_2") (pintype "passive"))
    )
    (net (code "44") (name "Net-(D9-GREEN)") (class "Default")
      (node (ref "D9") (pin "2") (pinfunction "GREEN_2") (pintype "bidirectional"))
      (node (ref "R30") (pin "2") (pinfunction "2_2") (pintype "passive"))
    )
    (net (code "45") (name "Net-(D9-RED)") (class "Default")
      (node (ref "D9") (pin "4") (pinfunction "RED_4") (pintype "bidirectional"))
      (node (ref "R39") (pin "2") (pinfunction "2_2") (pintype "passive"))
    )
    (net (code "46") (name "Net-(D10-BLUE)") (class "Default")
      (node (ref "D10") (pin "1") (pinfunction "BLUE_1") (pintype "bidirectional"))
      (node (ref "R21") (pin "2") (pinfunction "2_2") (pintype "passive"))
    )
    (net (code "47") (name "Net-(D10-GREEN)") (class "Default")
      (node (ref "D10") (pin "2") (pinfunction "GREEN_2") (pintype "bidirectional"))
      (node (ref "R28") (pin "2") (pinfunction "2_2") (pintype "passive"))
    )
    (net (code "48") (name "Net-(D10-RED)") (class "Default")
      (node (ref "D10") (pin "4") (pinfunction "RED_4") (pintype "bidirectional"))
      (node (ref "R40") (pin "2") (pinfunction "2_2") (pintype "passive"))
    )
    (net (code "49") (name "Net-(D11-BLUE)") (class "Default")
      (node (ref "D11") (pin "1") (pinfunction "BLUE_1") (pintype "bidirectional"))
      (node (ref "R22") (pin "2") (pinfunction "2_2") (pintype "passive"))
    )
    (net (code "50") (name "Net-(D11-GREEN)") (class "Default")
      (node (ref "D11") (pin "2") (pinfunction "GREEN_2") (pintype "bidirectional"))
      (node (ref "R47") (pin "2") (pinfunction "2_2") (pintype "passive"))
    )
    (net (code "51") (name "Net-(D11-RED)") (class "Default")
      (node (ref "D11") (pin "4") (pinfunction "RED_4") (pintype "bidirectional"))
      (node (ref "R41") (pin "2") (pinfunction "2_2") (pintype "passive"))
    )
    (net (code "52") (name "Net-(D12-BLUE)") (class "Default")
      (node (ref "D12") (pin "1") (pinfunction "BLUE_1") (pintype "bidirectional"))
      (node (ref "R23") (pin "2") (pinfunction "2_2") (pintype "passive"))
    )
    (net (code "53") (name "Net-(D12-GREEN)") (class "Default")
      (node (ref "D12") (pin "2") (pinfunction "GREEN_2") (pintype "bidirectional"))
      (node (ref "R48") (pin "2") (pinfunction "2_2") (pintype "passive"))
    )
    (net (code "54") (name "Net-(D12-RED)") (class "Default")
      (node (ref "D12") (pin "4") (pinfunction "RED_4") (pintype "bidirectional"))
      (node (ref "R42") (pin "2") (pinfunction "2_2") (pintype "passive"))
    )
    (net (code "55") (name "Net-(D13-BLUE)") (class "Default")
      (node (ref "D13") (pin "1") (pinfunction "BLUE_1") (pintype "bidirectional"))
      (node (ref "R24") (pin "2") (pinfunction "2_2") (pintype "passive"))
    )
    (net (code "56") (name "Net-(D13-GREEN)") (class "Default")
      (node (ref "D13") (pin "2") (pinfunction "GREEN_2") (pintype "bidirectional"))
      (node (ref "R49") (pin "2") (pinfunction "2_2") (pintype "passive"))
    )
    (net (code "57") (name "Net-(D13-RED)") (class "Default")
      (node (ref "D13") (pin "4") (pinfunction "RED_4") (pintype "bidirectional"))
      (node (ref "R43") (pin "2") (pinfunction "2_2") (pintype "passive"))
    )
    (net (code "58") (name "Net-(D14-BLUE)") (class "Default")
      (node (ref "D14") (pin "1") (pinfunction "BLUE_1") (pintype "bidirectional"))
      (node (ref "R25") (pin "2") (pinfunction "2_2") (pintype "passive"))
    )
    (net (code "59") (name "Net-(D14-GREEN)") (class "Default")
      (node (ref "D14") (pin "2") (pinfunction "GREEN_2") (pintype "bidirectional"))
      (node (ref "R50") (pin "2") (pinfunction "2_2") (pintype "passive"))
    )
    (net (code "60") (name "Net-(D14-RED)") (class "Default")
      (node (ref "D14") (pin "4") (pinfunction "RED_4") (pintype "bidirectional"))
      (node (ref "R44") (pin "2") (pinfunction "2_2") (pintype "passive"))
    )
    (net (code "61") (name "Net-(D15-BLUE)") (class "Default")
      (node (ref "D15") (pin "1") (pinfunction "BLUE_1") (pintype "bidirectional"))
      (node (ref "R26") (pin "2") (pinfunction "2_2") (pintype "passive"))
    )
    (net (code "62") (name "Net-(D15-GREEN)") (class "Default")
      (node (ref "D15") (pin "2") (pinfunction "GREEN_2") (pintype "bidirectional"))
      (node (ref "R51") (pin "2") (pinfunction "2_2") (pintype "passive"))
    )
    (net (code "63") (name "Net-(D15-RED)") (class "Default")
      (node (ref "D15") (pin "4") (pinfunction "RED_4") (pintype "bidirectional"))
      (node (ref "R45") (pin "2") (pinfunction "2_2") (pintype "passive"))
    )
    (net (code "64") (name "Net-(D16-BLUE)") (class "Default")
      (node (ref "D16") (pin "1") (pinfunction "BLUE_1") (pintype "bidirectional"))
      (node (ref "R27") (pin "2") (pinfunction "2_2") (pintype "passive"))
    )
    (net (code "65") (name "Net-(D16-GREEN)") (class "Default")
      (node (ref "D16") (pin "2") (pinfunction "GREEN_2") (pintype "bidirectional"))
      (node (ref "R52") (pin "2") (pinfunction "2_2") (pintype "passive"))
    )
    (net (code "66") (name "Net-(D16-RED)") (class "Default")
      (node (ref "D16") (pin "4") (pinfunction "RED_4") (pintype "bidirectional"))
      (node (ref "R46") (pin "2") (pinfunction "2_2") (pintype "passive"))
    )
    (net (code "67") (name "Net-(IC2-EN)") (class "Default")
      (node (ref "BATT") (pin "TP") (pinfunction "TP_TP") (pintype "input"))
      (node (ref "C1") (pin "2") (pinfunction "2_2") (pintype "passive"))
      (node (ref "IC2") (pin "3") (pinfunction "EN_3") (pintype "input"))
      (node (ref "IC2") (pin "6") (pinfunction "VBAT_6") (pintype "input"))
      (node (ref "L1") (pin "2") (pinfunction "2_2") (pintype "passive"))
      (node (ref "X1") (pin "2") (pinfunction "2_2") (pintype "passive"))
    )
    (net (code "68") (name "Net-(IC2-FB)") (class "Default")
      (node (ref "IC2") (pin "4") (pinfunction "FB_4") (pintype "input"))
      (node (ref "R1") (pin "1") (pinfunction "1_1") (pintype "passive"))
      (node (ref "R2") (pin "2") (pinfunction "2_2") (pintype "passive"))
    )
    (net (code "69") (name "Net-(IC2-SW)") (class "Default")
      (node (ref "IC2") (pin "1") (pinfunction "SW_1") (pintype "input"))
      (node (ref "L1") (pin "1") (pinfunction "1_1") (pintype "passive"))
    )
    (net (code "70") (name "Net-(R3-Pad2)") (class "Default")
      (node (ref "R3") (pin "2") (pinfunction "2_2") (pintype "passive"))
      (node (ref "U2") (pin "3") (pinfunction "3_3") (pintype "passive"))
    )
    (net (code "71") (name "Net-(R4-Pad2)") (class "Default")
      (node (ref "R4") (pin "2") (pinfunction "2_2") (pintype "passive"))
      (node (ref "U3") (pin "3") (pinfunction "3_3") (pintype "passive"))
    )
    (net (code "72") (name "Net-(U1-PB1)") (class "Default")
      (node (ref "DWM_RST") (pin "TP") (pinfunction "TP_TP") (pintype "input"))
      (node (ref "U1") (pin "13") (pinfunction "PB1_13") (pintype "bidirectional"))
      (node (ref "U4") (pin "3") (pinfunction "RSTN_3") (pintype "bidirectional"))
    )
    (net (code "73") (name "Net-(U1-PB2)") (class "Default")
      (node (ref "SPI_CS") (pin "TP") (pinfunction "TP_TP") (pintype "input"))
      (node (ref "U1") (pin "14") (pinfunction "PB2_14") (pintype "bidirectional"))
      (node (ref "U4") (pin "17") (pinfunction "SPICSN_17") (pintype "input"))
    )
    (net (code "74") (name "Net-(U1-PB3)") (class "Default")
      (node (ref "JP1") (pin "4") (pinfunction "4_4") (pintype "passive"))
      (node (ref "MOSI") (pin "TP") (pinfunction "TP_TP") (pintype "input"))
      (node (ref "R53") (pin "1") (pinfunction "1_1") (pintype "passive"))
      (node (ref "U1") (pin "15") (pinfunction "PB3_15") (pintype "bidirectional"))
    )
    (net (code "75") (name "Net-(U1-PB4)") (class "Default")
      (node (ref "JP1") (pin "1") (pinfunction "1_1") (pintype "passive"))
      (node (ref "MISO") (pin "TP") (pinfunction "TP_TP") (pintype "input"))
      (node (ref "R55") (pin "1") (pinfunction "1_1") (pintype "passive"))
      (node (ref "U1") (pin "16") (pinfunction "PB4_16") (pintype "bidirectional"))
    )
    (net (code "76") (name "Net-(U1-PB5)") (class "Default")
      (node (ref "JP1") (pin "3") (pinfunction "3_3") (pintype "passive"))
      (node (ref "R54") (pin "1") (pinfunction "1_1") (pintype "passive"))
      (node (ref "SPI_CLK") (pin "TP") (pinfunction "TP_TP") (pintype "input"))
      (node (ref "U1") (pin "17") (pinfunction "PB5_17") (pintype "bidirectional"))
    )
    (net (code "77") (name "Net-(U1-PB6)") (class "Default")
      (node (ref "U1") (pin "7") (pinfunction "PB6_7") (pintype "bidirectional"))
      (node (ref "Y1") (pin "1") (pinfunction "IN_1") (pintype "input"))
    )
    (net (code "78") (name "Net-(U1-PB7)") (class "Default")
      (node (ref "U1") (pin "8") (pinfunction "PB7_8") (pintype "bidirectional"))
      (node (ref "Y1") (pin "3") (pinfunction "OUT_3") (pintype "output"))
    )
    (net (code "79") (name "Net-(U1-PC6{slash}~{RESET})") (class "Default")
      (node (ref "JP1") (pin "5") (pinfunction "5_5") (pintype "passive"))
      (node (ref "JP3") (pin "6") (pinfunction "6_6") (pintype "passive"))
      (node (ref "R60") (pin "1") (pinfunction "1_1") (pintype "passive"))
      (node (ref "U1") (pin "29") (pinfunction "PC6/~{RESET}_29") (pintype "bidirectional"))
    )
    (net (code "80") (name "Net-(U1-PD2)") (class "Default")
      (node (ref "DWM_IRQ") (pin "TP") (pinfunction "TP_TP") (pintype "input"))
      (node (ref "JP3") (pin "5") (pinfunction "5_5") (pintype "passive"))
      (node (ref "U1") (pin "32") (pinfunction "PD2_32") (pintype "bidirectional"))
      (node (ref "U4") (pin "22") (pinfunction "IRQ/GPIO8_22") (pintype "bidirectional"))
    )
    (net (code "81") (name "Net-(U1-PD3)") (class "Default")
      (node (ref "R56") (pin "2") (pinfunction "2_2") (pintype "passive"))
      (node (ref "TONE") (pin "TP") (pinfunction "TP_TP") (pintype "input"))
      (node (ref "U1") (pin "1") (pinfunction "PD3_1") (pintype "bidirectional"))
      (node (ref "U5") (pin "3") (pinfunction "NON-INVERTING_INPUT_3") (pintype "input"))
    )
    (net (code "82") (name "Net-(U4-EXTON)") (class "Default")
      (node (ref "EXTON") (pin "TP") (pinfunction "TP_TP") (pintype "input"))
      (node (ref "U4") (pin "1") (pinfunction "EXTON_1") (pintype "output"))
    )
    (net (code "83") (name "Net-(U4-GPIO0)") (class "Default")
      (node (ref "DWM_GP0") (pin "TP") (pinfunction "TP_TP") (pintype "input"))
      (node (ref "U4") (pin "15") (pinfunction "GPIO0_15") (pintype "bidirectional"))
    )
    (net (code "84") (name "Net-(U4-GPIO1)") (class "Default")
      (node (ref "DWM_GP1") (pin "TP") (pinfunction "TP_TP") (pintype "input"))
      (node (ref "U4") (pin "14") (pinfunction "GPIO1_14") (pintype "bidirectional"))
    )
    (net (code "85") (name "Net-(U4-GPIO2)") (class "Default")
      (node (ref "DWM_GP2") (pin "TP") (pinfunction "TP_TP") (pintype "input"))
      (node (ref "U4") (pin "13") (pinfunction "GPIO2_13") (pintype "bidirectional"))
    )
    (net (code "86") (name "Net-(U4-GPIO3)") (class "Default")
      (node (ref "DWM_GP3") (pin "TP") (pinfunction "TP_TP") (pintype "input"))
      (node (ref "U4") (pin "12") (pinfunction "GPIO3_12") (pintype "bidirectional"))
    )
    (net (code "87") (name "Net-(U4-GPIO4)") (class "Default")
      (node (ref "DWM_GP4") (pin "TP") (pinfunction "TP_TP") (pintype "input"))
      (node (ref "U4") (pin "11") (pinfunction "GPIO4_11") (pintype "bidirectional"))
    )
    (net (code "88") (name "Net-(U4-GPIO5)") (class "Default")
      (node (ref "DWM_GP5") (pin "TP") (pinfunction "TP_TP") (pintype "input"))
      (node (ref "U4") (pin "10") (pinfunction "GPIO5_10") (pintype "bidirectional"))
    )
    (net (code "89") (name "Net-(U4-GPIO6)") (class "Default")
      (node (ref "DWM_GP6") (pin "TP") (pinfunction "TP_TP") (pintype "input"))
      (node (ref "U4") (pin "9") (pinfunction "GPIO6_9") (pintype "bidirectional"))
    )
    (net (code "90") (name "Net-(U4-GPIO7)") (class "Default")
      (node (ref "DWM_GP7") (pin "TP") (pinfunction "TP_TP") (pintype "input"))
      (node (ref "U4") (pin "4") (pinfunction "GPIO7_4") (pintype "bidirectional"))
    )
    (net (code "91") (name "Net-(U4-SPICLK)") (class "Default")
      (node (ref "R54") (pin "2") (pinfunction "2_2") (pintype "passive"))
      (node (ref "U4") (pin "20") (pinfunction "SPICLK_20") (pintype "input"))
    )
    (net (code "92") (name "Net-(U4-SPIMISO)") (class "Default")
      (node (ref "R55") (pin "2") (pinfunction "2_2") (pintype "passive"))
      (node (ref "U4") (pin "19") (pinfunction "SPIMISO_19") (pintype "output"))
    )
    (net (code "93") (name "Net-(U4-SPIMOSI)") (class "Default")
      (node (ref "R53") (pin "2") (pinfunction "2_2") (pintype "passive"))
      (node (ref "U4") (pin "18") (pinfunction "SPIMOSI_18") (pintype "input"))
    )
    (net (code "94") (name "Net-(U4-WAKEUP)") (class "Default")
      (node (ref "U4") (pin "2") (pinfunction "WAKEUP_2") (pintype "bidirectional"))
      (node (ref "WKUP") (pin "TP") (pinfunction "TP_TP") (pintype "input"))
    )
    (net (code "95") (name "Net-(U5-INVERTING_INPUT)") (class "Default")
      (node (ref "C3") (pin "2") (pinfunction "2_2") (pintype "passive"))
      (node (ref "R57") (pin "2") (pinfunction "2_2") (pintype "passive"))
      (node (ref "R58") (pin "2") (pinfunction "2_2") (pintype "passive"))
      (node (ref "U5") (pin "2") (pinfunction "INVERTING_INPUT_2") (pintype "input"))
    )
    (net (code "96") (name "Net-(U5-OUTPUT)") (class "Default")
      (node (ref "C3") (pin "1") (pinfunction "1_1") (pintype "passive"))
      (node (ref "L2") (pin "1") (pinfunction "1_1") (pintype "passive"))
      (node (ref "R57") (pin "1") (pinfunction "1_1") (pintype "passive"))
      (node (ref "U5") (pin "6") (pinfunction "OUTPUT_6") (pintype "output"))
    )
    (net (code "97") (name "Net-(U6-0)") (class "Default")
      (node (ref "R12") (pin "1") (pinfunction "1_1") (pintype "passive"))
      (node (ref "U6") (pin "1") (pinfunction "0_1") (pintype "output"))
    )
    (net (code "98") (name "Net-(U6-1)") (class "Default")
      (node (ref "R13") (pin "1") (pinfunction "1_1") (pintype "passive"))
      (node (ref "U6") (pin "2") (pinfunction "1_2") (pintype "output"))
    )
    (net (code "99") (name "Net-(U6-2)") (class "Default")
      (node (ref "R14") (pin "1") (pinfunction "1_1") (pintype "passive"))
      (node (ref "U6") (pin "3") (pinfunction "2_3") (pintype "output"))
    )
    (net (code "100") (name "Net-(U6-3)") (class "Default")
      (node (ref "R15") (pin "1") (pinfunction "1_1") (pintype "passive"))
      (node (ref "U6") (pin "4") (pinfunction "3_4") (pintype "output"))
    )
    (net (code "101") (name "Net-(U6-4)") (class "Default")
      (node (ref "R16") (pin "1") (pinfunction "1_1") (pintype "passive"))
      (node (ref "U6") (pin "5") (pinfunction "4_5") (pintype "output"))
    )
    (net (code "102") (name "Net-(U6-5)") (class "Default")
      (node (ref "R17") (pin "1") (pinfunction "1_1") (pintype "passive"))
      (node (ref "U6") (pin "6") (pinfunction "5_6") (pintype "output"))
    )
    (net (code "103") (name "Net-(U6-6)") (class "Default")
      (node (ref "R18") (pin "1") (pinfunction "1_1") (pintype "passive"))
      (node (ref "U6") (pin "7") (pinfunction "6_7") (pintype "output"))
    )
    (net (code "104") (name "Net-(U6-7)") (class "Default")
      (node (ref "R19") (pin "1") (pinfunction "1_1") (pintype "passive"))
      (node (ref "U6") (pin "8") (pinfunction "7_8") (pintype "output"))
    )
    (net (code "105") (name "Net-(U6-8)") (class "Default")
      (node (ref "R20") (pin "1") (pinfunction "1_1") (pintype "passive"))
      (node (ref "U6") (pin "9") (pinfunction "8_9") (pintype "output"))
    )
    (net (code "106") (name "Net-(U6-9)") (class "Default")
      (node (ref "R21") (pin "1") (pinfunction "1_1") (pintype "passive"))
      (node (ref "U6") (pin "10") (pinfunction "9_10") (pintype "output"))
    )
    (net (code "107") (name "Net-(U6-10)") (class "Default")
      (node (ref "R22") (pin "1") (pinfunction "1_1") (pintype "passive"))
      (node (ref "U6") (pin "11") (pinfunction "10_11") (pintype "output"))
    )
    (net (code "108") (name "Net-(U6-11)") (class "Default")
      (node (ref "R23") (pin "1") (pinfunction "1_1") (pintype "passive"))
      (node (ref "U6") (pin "13") (pinfunction "11_13") (pintype "output"))
    )
    (net (code "109") (name "Net-(U6-12)") (class "Default")
      (node (ref "R24") (pin "1") (pinfunction "1_1") (pintype "passive"))
      (node (ref "U6") (pin "14") (pinfunction "12_14") (pintype "output"))
    )
    (net (code "110") (name "Net-(U6-13)") (class "Default")
      (node (ref "R25") (pin "1") (pinfunction "1_1") (pintype "passive"))
      (node (ref "U6") (pin "15") (pinfunction "13_15") (pintype "output"))
    )
    (net (code "111") (name "Net-(U6-14)") (class "Default")
      (node (ref "R26") (pin "1") (pinfunction "1_1") (pintype "passive"))
      (node (ref "U6") (pin "16") (pinfunction "14_16") (pintype "output"))
    )
    (net (code "112") (name "Net-(U6-15)") (class "Default")
      (node (ref "R27") (pin "1") (pinfunction "1_1") (pintype "passive"))
      (node (ref "U6") (pin "17") (pinfunction "15_17") (pintype "output"))
    )
    (net (code "113") (name "Net-(U7-0)") (class "Default")
      (node (ref "R5") (pin "1") (pinfunction "1_1") (pintype "passive"))
      (node (ref "U7") (pin "1") (pinfunction "0_1") (pintype "output"))
    )
    (net (code "114") (name "Net-(U7-1)") (class "Default")
      (node (ref "R6") (pin "1") (pinfunction "1_1") (pintype "passive"))
      (node (ref "U7") (pin "2") (pinfunction "1_2") (pintype "output"))
    )
    (net (code "115") (name "Net-(U7-2)") (class "Default")
      (node (ref "R7") (pin "1") (pinfunction "1_1") (pintype "passive"))
      (node (ref "U7") (pin "3") (pinfunction "2_3") (pintype "output"))
    )
    (net (code "116") (name "Net-(U7-3)") (class "Default")
      (node (ref "R8") (pin "1") (pinfunction "1_1") (pintype "passive"))
      (node (ref "U7") (pin "4") (pinfunction "3_4") (pintype "output"))
    )
    (net (code "117") (name "Net-(U7-4)") (class "Default")
      (node (ref "R9") (pin "1") (pinfunction "1_1") (pintype "passive"))
      (node (ref "U7") (pin "5") (pinfunction "4_5") (pintype "output"))
    )
    (net (code "118") (name "Net-(U7-5)") (class "Default")
      (node (ref "R10") (pin "1") (pinfunction "1_1") (pintype "passive"))
      (node (ref "U7") (pin "6") (pinfunction "5_6") (pintype "output"))
    )
    (net (code "119") (name "Net-(U7-6)") (class "Default")
      (node (ref "R11") (pin "1") (pinfunction "1_1") (pintype "passive"))
      (node (ref "U7") (pin "7") (pinfunction "6_7") (pintype "output"))
    )
    (net (code "120") (name "Net-(U7-7)") (class "Default")
      (node (ref "R29") (pin "1") (pinfunction "1_1") (pintype "passive"))
      (node (ref "U7") (pin "8") (pinfunction "7_8") (pintype "output"))
    )
    (net (code "121") (name "Net-(U7-8)") (class "Default")
      (node (ref "R30") (pin "1") (pinfunction "1_1") (pintype "passive"))
      (node (ref "U7") (pin "9") (pinfunction "8_9") (pintype "output"))
    )
    (net (code "122") (name "Net-(U7-9)") (class "Default")
      (node (ref "R28") (pin "1") (pinfunction "1_1") (pintype "passive"))
      (node (ref "U7") (pin "10") (pinfunction "9_10") (pintype "output"))
    )
    (net (code "123") (name "Net-(U7-10)") (class "Default")
      (node (ref "R47") (pin "1") (pinfunction "1_1") (pintype "passive"))
      (node (ref "U7") (pin "11") (pinfunction "10_11") (pintype "output"))
    )
    (net (code "124") (name "Net-(U7-11)") (class "Default")
      (node (ref "R48") (pin "1") (pinfunction "1_1") (pintype "passive"))
      (node (ref "U7") (pin "13") (pinfunction "11_13") (pintype "output"))
    )
    (net (code "125") (name "Net-(U7-12)") (class "Default")
      (node (ref "R49") (pin "1") (pinfunction "1_1") (pintype "passive"))
      (node (ref "U7") (pin "14") (pinfunction "12_14") (pintype "output"))
    )
    (net (code "126") (name "Net-(U7-13)") (class "Default")
      (node (ref "R50") (pin "1") (pinfunction "1_1") (pintype "passive"))
      (node (ref "U7") (pin "15") (pinfunction "13_15") (pintype "output"))
    )
    (net (code "127") (name "Net-(U7-14)") (class "Default")
      (node (ref "R51") (pin "1") (pinfunction "1_1") (pintype "passive"))
      (node (ref "U7") (pin "16") (pinfunction "14_16") (pintype "output"))
    )
    (net (code "128") (name "Net-(U7-15)") (class "Default")
      (node (ref "R52") (pin "1") (pinfunction "1_1") (pintype "passive"))
      (node (ref "U7") (pin "17") (pinfunction "15_17") (pintype "output"))
    )
    (net (code "129") (name "Net-(U8-0)") (class "Default")
      (node (ref "R31") (pin "1") (pinfunction "1_1") (pintype "passive"))
      (node (ref "U8") (pin "1") (pinfunction "0_1") (pintype "output"))
    )
    (net (code "130") (name "Net-(U8-1)") (class "Default")
      (node (ref "R32") (pin "1") (pinfunction "1_1") (pintype "passive"))
      (node (ref "U8") (pin "2") (pinfunction "1_2") (pintype "output"))
    )
    (net (code "131") (name "Net-(U8-2)") (class "Default")
      (node (ref "R33") (pin "1") (pinfunction "1_1") (pintype "passive"))
      (node (ref "U8") (pin "3") (pinfunction "2_3") (pintype "output"))
    )
    (net (code "132") (name "Net-(U8-3)") (class "Default")
      (node (ref "R34") (pin "1") (pinfunction "1_1") (pintype "passive"))
      (node (ref "U8") (pin "4") (pinfunction "3_4") (pintype "output"))
    )
    (net (code "133") (name "Net-(U8-4)") (class "Default")
      (node (ref "R35") (pin "1") (pinfunction "1_1") (pintype "passive"))
      (node (ref "U8") (pin "5") (pinfunction "4_5") (pintype "output"))
    )
    (net (code "134") (name "Net-(U8-5)") (class "Default")
      (node (ref "R36") (pin "1") (pinfunction "1_1") (pintype "passive"))
      (node (ref "U8") (pin "6") (pinfunction "5_6") (pintype "output"))
    )
    (net (code "135") (name "Net-(U8-6)") (class "Default")
      (node (ref "R37") (pin "1") (pinfunction "1_1") (pintype "passive"))
      (node (ref "U8") (pin "7") (pinfunction "6_7") (pintype "output"))
    )
    (net (code "136") (name "Net-(U8-7)") (class "Default")
      (node (ref "R38") (pin "1") (pinfunction "1_1") (pintype "passive"))
      (node (ref "U8") (pin "8") (pinfunction "7_8") (pintype "output"))
    )
    (net (code "137") (name "Net-(U8-8)") (class "Default")
      (node (ref "R39") (pin "1") (pinfunction "1_1") (pintype "passive"))
      (node (ref "U8") (pin "9") (pinfunction "8_9") (pintype "output"))
    )
    (net (code "138") (name "Net-(U8-9)") (class "Default")
      (node (ref "R40") (pin "1") (pinfunction "1_1") (pintype "passive"))
      (node (ref "U8") (pin "10") (pinfunction "9_10") (pintype "output"))
    )
    (net (code "139") (name "Net-(U8-10)") (class "Default")
      (node (ref "R41") (pin "1") (pinfunction "1_1") (pintype "passive"))
      (node (ref "U8") (pin "11") (pinfunction "10_11") (pintype "output"))
    )
    (net (code "140") (name "Net-(U8-11)") (class "Default")
      (node (ref "R42") (pin "1") (pinfunction "1_1") (pintype "passive"))
      (node (ref "U8") (pin "13") (pinfunction "11_13") (pintype "output"))
    )
    (net (code "141") (name "Net-(U8-12)") (class "Default")
      (node (ref "R43") (pin "1") (pinfunction "1_1") (pintype "passive"))
      (node (ref "U8") (pin "14") (pinfunction "12_14") (pintype "output"))
    )
    (net (code "142") (name "Net-(U8-13)") (class "Default")
      (node (ref "R44") (pin "1") (pinfunction "1_1") (pintype "passive"))
      (node (ref "U8") (pin "15") (pinfunction "13_15") (pintype "output"))
    )
    (net (code "143") (name "Net-(U8-14)") (class "Default")
      (node (ref "R45") (pin "1") (pinfunction "1_1") (pintype "passive"))
      (node (ref "U8") (pin "16") (pinfunction "14_16") (pintype "output"))
    )
    (net (code "144") (name "Net-(U8-15)") (class "Default")
      (node (ref "R46") (pin "1") (pinfunction "1_1") (pintype "passive"))
      (node (ref "U8") (pin "17") (pinfunction "15_17") (pintype "output"))
    )
    (net (code "145") (name "VCC") (class "Default")
      (node (ref "C2") (pin "2") (pinfunction "2_2") (pintype "passive"))
      (node (ref "D1") (pin "3") (pinfunction "VCC_3") (pintype "bidirectional"))
      (node (ref "D10") (pin "3") (pinfunction "VCC_3") (pintype "bidirectional"))
      (node (ref "D11") (pin "3") (pinfunction "VCC_3") (pintype "bidirectional"))
      (node (ref "D12") (pin "3") (pinfunction "VCC_3") (pintype "bidirectional"))
      (node (ref "D13") (pin "3") (pinfunction "VCC_3") (pintype "bidirectional"))
      (node (ref "D14") (pin "3") (pinfunction "VCC_3") (pintype "bidirectional"))
      (node (ref "D15") (pin "3") (pinfunction "VCC_3") (pintype "bidirectional"))
      (node (ref "D16") (pin "3") (pinfunction "VCC_3") (pintype "bidirectional"))
      (node (ref "D2") (pin "3") (pinfunction "VCC_3") (pintype "bidirectional"))
      (node (ref "D3") (pin "3") (pinfunction "VCC_3") (pintype "bidirectional"))
      (node (ref "D4") (pin "3") (pinfunction "VCC_3") (pintype "bidirectional"))
      (node (ref "D5") (pin "3") (pinfunction "VCC_3") (pintype "bidirectional"))
      (node (ref "D6") (pin "3") (pinfunction "VCC_3") (pintype "bidirectional"))
      (node (ref "D7") (pin "3") (pinfunction "VCC_3") (pintype "bidirectional"))
      (node (ref "D8") (pin "3") (pinfunction "VCC_3") (pintype "bidirectional"))
      (node (ref "D9") (pin "3") (pinfunction "VCC_3") (pintype "bidirectional"))
      (node (ref "IC2") (pin "5") (pinfunction "VOUT_5") (pintype "passive"))
      (node (ref "JP1") (pin "2") (pinfunction "2_2") (pintype "passive"))
      (node (ref "JP3") (pin "3") (pinfunction "3_3") (pintype "passive"))
      (node (ref "R1") (pin "2") (pinfunction "2_2") (pintype "passive"))
      (node (ref "R3") (pin "1") (pinfunction "1_1") (pintype "passive"))
      (node (ref "R4") (pin "1") (pinfunction "1_1") (pintype "passive"))
      (node (ref "R59") (pin "2") (pinfunction "2_2") (pintype "passive"))
      (node (ref "R60") (pin "2") (pinfunction "2_2") (pintype "passive"))
      (node (ref "U1") (pin "18") (pinfunction "AVCC_18") (pintype "power_in"))
      (node (ref "U1") (pin "20") (pinfunction "AREF_20") (pintype "input"))
      (node (ref "U1") (pin "4") (pinfunction "VCC_4") (pintype "power_in"))
      (node (ref "U1") (pin "6") (pinfunction "VCC_6") (pintype "power_in"))
      (node (ref "U4") (pin "5") (pinfunction "VDDAON_5") (pintype "power_in"))
      (node (ref "U4") (pin "6") (pinfunction "VDD3V3_6") (pintype "power_in"))
      (node (ref "U4") (pin "7") (pinfunction "VDD3V3_7") (pintype "power_in"))
      (node (ref "U5") (pin "7") (pinfunction "VCC+_7") (pintype "power_in"))
      (node (ref "U6") (pin "24") (pinfunction "VCC_24") (pintype "power_in"))
      (node (ref "U7") (pin "24") (pinfunction "VCC_24") (pintype "power_in"))
      (node (ref "U8") (pin "24") (pinfunction "VCC_24") (pintype "power_in"))
      (node (ref "VCC") (pin "TP") (pinfunction "TP_TP") (pintype "input"))
    )
    (net (code "146") (name "unconnected-(JP3-Pad2)") (class "Default")
      (node (ref "JP3") (pin "2") (pinfunction "2_2") (pintype "passive"))
    )
    (net (code "147") (name "unconnected-(U2-Pad2)") (class "Default")
      (node (ref "U2") (pin "2") (pinfunction "2_2") (pintype "passive"))
    )
    (net (code "148") (name "unconnected-(U3-Pad2)") (class "Default")
      (node (ref "U3") (pin "2") (pinfunction "2_2") (pintype "passive"))
    )
    (net (code "149") (name "unconnected-(U5-OFFSET_NULL_1-Pad1)") (class "Default")
      (node (ref "U5") (pin "1") (pinfunction "OFFSET_NULL_1_1") (pintype "passive"))
    )
    (net (code "150") (name "unconnected-(U5-OFFSET_NULL_2-Pad5)") (class "Default")
      (node (ref "U5") (pin "5") (pinfunction "OFFSET_NULL_2_5") (pintype "passive"))
    )
  )
)
